# spi_lcd_v1.net
KiCad netlist of a schematic drawn in EAGLE
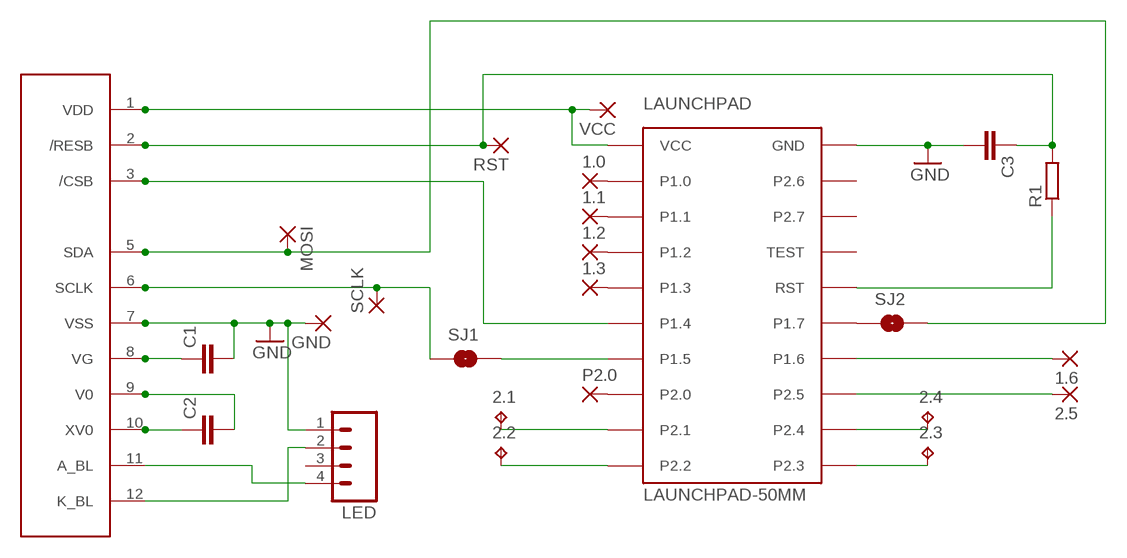
[diagram p0: schematic, sheet 1]

(export (version "E")
  (design (tool "Eeschema 10.0.6"))
  (components
    (comp (ref "1.0")
      (value "2,15/1,0")
      (footprint "eagle-import:2,15_1,0")
      (libsource (lib "eagle-import") (part "2,15/1,0"))
    )
    (comp (ref "1.1")
      (value "2,15/1,0")
      (footprint "eagle-import:2,15_1,0")
      (libsource (lib "eagle-import") (part "2,15/1,0"))
    )
    (comp (ref "1.2")
      (value "2,15/1,0")
      (footprint "eagle-import:2,15_1,0")
      (libsource (lib "eagle-import") (part "2,15/1,0"))
    )
    (comp (ref "1.3")
      (value "2,15/1,0")
      (footprint "eagle-import:2,15_1,0")
      (libsource (lib "eagle-import") (part "2,15/1,0"))
    )
    (comp (ref "1.6")
      (value "2,15/1,0")
      (footprint "eagle-import:2,15_1,0")
      (libsource (lib "eagle-import") (part "2,15/1,0"))
    )
    (comp (ref "2.1")
      (value "TPTP07R")
      (footprint "eagle-import:TP07R")
      (libsource (lib "eagle-import") (part "TPTP07R"))
    )
    (comp (ref "2.2")
      (value "TPTP07R")
      (footprint "eagle-import:TP07R")
      (libsource (lib "eagle-import") (part "TPTP07R"))
    )
    (comp (ref "2.3")
      (value "TPTP07R")
      (footprint "eagle-import:TP07R")
      (libsource (lib "eagle-import") (part "TPTP07R"))
    )
    (comp (ref "2.4")
      (value "TPTP07R")
      (footprint "eagle-import:TP07R")
      (libsource (lib "eagle-import") (part "TPTP07R"))
    )
    (comp (ref "2.5")
      (value "2,15/1,0")
      (footprint "eagle-import:2,15_1,0")
      (libsource (lib "eagle-import") (part "2,15/1,0"))
    )
    (comp (ref "C1")
      (value "CAP1206")
      (footprint "eagle-import:1206")
      (libsource (lib "eagle-import") (part "CAP1206"))
    )
    (comp (ref "C2")
      (value "CAP1206")
      (footprint "eagle-import:1206")
      (libsource (lib "eagle-import") (part "CAP1206"))
    )
    (comp (ref "C3")
      (value "CAP1206")
      (footprint "eagle-import:1206")
      (libsource (lib "eagle-import") (part "CAP1206"))
    )
    (comp (ref "GND")
      (value "2,15/1,0")
      (footprint "eagle-import:2,15_1,0")
      (libsource (lib "eagle-import") (part "2,15/1,0"))
    )
    (comp (ref "LAUNCHPAD")
      (value "LAUNCHPAD-50MM")
      (footprint "eagle-import:LAUNCHPAD-50MM")
      (libsource (lib "eagle-import") (part "LAUNCHPAD-50MM"))
    )
    (comp (ref "LED")
      (value "M04PTH")
      (footprint "eagle-import:1X04")
      (libsource (lib "eagle-import") (part "M04PTH"))
    )
    (comp (ref "MOSI")
      (value "2,15/1,0")
      (footprint "eagle-import:2,15_1,0")
      (libsource (lib "eagle-import") (part "2,15/1,0"))
    )
    (comp (ref "P2.0")
      (value "2,15/1,0")
      (footprint "eagle-import:2,15_1,0")
      (libsource (lib "eagle-import") (part "2,15/1,0"))
    )
    (comp (ref "R1")
      (value "R-EU_R1206")
      (footprint "eagle-import:R1206")
      (libsource (lib "eagle-import") (part "R-EU_R1206"))
    )
    (comp (ref "RST")
      (value "2,15/1,0")
      (footprint "eagle-import:2,15_1,0")
      (libsource (lib "eagle-import") (part "2,15/1,0"))
    )
    (comp (ref "SCLK")
      (value "2,15/1,0")
      (footprint "eagle-import:2,15_1,0")
      (libsource (lib "eagle-import") (part "2,15/1,0"))
    )
    (comp (ref "SJ1")
      (value "SOLDERJUMPERTRACE")
      (footprint "eagle-import:SJ_2S-TRACE")
      (libsource (lib "eagle-import") (part "SOLDERJUMPERTRACE"))
    )
    (comp (ref "SJ2")
      (value "SOLDERJUMPERTRACE")
      (footprint "eagle-import:SJ_2S-TRACE")
      (libsource (lib "eagle-import") (part "SOLDERJUMPERTRACE"))
    )
    (comp (ref "U$1")
      (value "PE9665WRFPE9665WRF-WHOLE")
      (footprint "eagle-import:PE9665WRF")
      (libsource (lib "eagle-import") (part "PE9665WRFPE9665WRF-WHOLE"))
    )
    (comp (ref "VCC")
      (value "2,15/1,0")
      (footprint "eagle-import:2,15_1,0")
      (libsource (lib "eagle-import") (part "2,15/1,0"))
    )
  )
  (nets
    (net (code "1") (name "GND") (class "Default")
      (node (ref "C1") (pin "2") (pinfunction "2_2") (pintype "passive"))
      (node (ref "C3") (pin "2") (pinfunction "2_2") (pintype "passive"))
      (node (ref "GND") (pin "1") (pinfunction "P_1") (pintype "passive"))
      (node (ref "LAUNCHPAD") (pin "GND") (pinfunction "GND_GND") (pintype "power_in"))
      (node (ref "LED") (pin "1") (pinfunction "1_1") (pintype "passive"))
      (node (ref "U$1") (pin "7") (pinfunction "VSS_7") (pintype "bidirectional"))
    )
    (net (code "2") (name "Net-(1.0-P)") (class "Default")
      (node (ref "1.0") (pin "1") (pinfunction "P_1") (pintype "passive"))
      (node (ref "LAUNCHPAD") (pin "P1.0") (pinfunction "P1.0_P1.0") (pintype "bidirectional"))
    )
    (net (code "3") (name "Net-(1.1-P)") (class "Default")
      (node (ref "1.1") (pin "1") (pinfunction "P_1") (pintype "passive"))
      (node (ref "LAUNCHPAD") (pin "P1.1") (pinfunction "P1.1_P1.1") (pintype "bidirectional"))
    )
    (net (code "4") (name "Net-(1.2-P)") (class "Default")
      (node (ref "1.2") (pin "1") (pinfunction "P_1") (pintype "passive"))
      (node (ref "LAUNCHPAD") (pin "P1.2") (pinfunction "P1.2_P1.2") (pintype "bidirectional"))
    )
    (net (code "5") (name "Net-(1.3-P)") (class "Default")
      (node (ref "1.3") (pin "1") (pinfunction "P_1") (pintype "passive"))
      (node (ref "LAUNCHPAD") (pin "P1.3") (pinfunction "P1.3_P1.3") (pintype "bidirectional"))
    )
    (net (code "6") (name "Net-(1.6-P)") (class "Default")
      (node (ref "1.6") (pin "1") (pinfunction "P_1") (pintype "passive"))
      (node (ref "LAUNCHPAD") (pin "P1.6") (pinfunction "P1.6_P1.6") (pintype "bidirectional"))
    )
    (net (code "7") (name "Net-(2.1-PadTP)") (class "Default")
      (node (ref "2.1") (pin "TP") (pinfunction "TP_TP") (pintype "input"))
      (node (ref "LAUNCHPAD") (pin "P2.1") (pinfunction "P2.1_P2.1") (pintype "bidirectional"))
    )
    (net (code "8") (name "Net-(2.2-PadTP)") (class "Default")
      (node (ref "2.2") (pin "TP") (pinfunction "TP_TP") (pintype "input"))
      (node (ref "LAUNCHPAD") (pin "P2.2") (pinfunction "P2.2_P2.2") (pintype "bidirectional"))
    )
    (net (code "9") (name "Net-(2.3-PadTP)") (class "Default")
      (node (ref "2.3") (pin "TP") (pinfunction "TP_TP") (pintype "input"))
      (node (ref "LAUNCHPAD") (pin "P2.3") (pinfunction "P2.3_P2.3") (pintype "bidirectional"))
    )
    (net (code "10") (name "Net-(2.4-PadTP)") (class "Default")
      (node (ref "2.4") (pin "TP") (pinfunction "TP_TP") (pintype "input"))
      (node (ref "LAUNCHPAD") (pin "P2.4") (pinfunction "P2.4_P2.4") (pintype "bidirectional"))
    )
    (net (code "11") (name "Net-(2.5-P)") (class "Default")
      (node (ref "2.5") (pin "1") (pinfunction "P_1") (pintype "passive"))
      (node (ref "LAUNCHPAD") (pin "P2.5") (pinfunction "P2.5_P2.5") (pintype "bidirectional"))
    )
    (net (code "12") (name "Net-(LAUNCHPAD-PadP1.5)") (class "Default")
      (node (ref "LAUNCHPAD") (pin "P1.5") (pinfunction "P1.5_P1.5") (pintype "bidirectional"))
      (node (ref "SJ1") (pin "2") (pinfunction "2_2") (pintype "passive"))
    )
    (net (code "13") (name "Net-(LAUNCHPAD-PadP1.7)") (class "Default")
      (node (ref "LAUNCHPAD") (pin "P1.7") (pinfunction "P1.7_P1.7") (pintype "bidirectional"))
      (node (ref "SJ2") (pin "1") (pinfunction "1_1") (pintype "passive"))
    )
    (net (code "14") (name "Net-(LAUNCHPAD-PadRST)") (class "Default")
      (node (ref "LAUNCHPAD") (pin "RST") (pinfunction "RST_RST") (pintype "bidirectional"))
      (node (ref "R1") (pin "1") (pinfunction "1_1") (pintype "passive"))
    )
    (net (code "15") (name "Net-(MOSI-P)") (class "Default")
      (node (ref "MOSI") (pin "1") (pinfunction "P_1") (pintype "passive"))
      (node (ref "SJ2") (pin "2") (pinfunction "2_2") (pintype "passive"))
      (node (ref "U$1") (pin "5") (pinfunction "SDA_5") (pintype "bidirectional"))
    )
    (net (code "16") (name "Net-(P2.0-P)") (class "Default")
      (node (ref "LAUNCHPAD") (pin "P2.0") (pinfunction "P2.0_P2.0") (pintype "bidirectional"))
      (node (ref "P2.0") (pin "1") (pinfunction "P_1") (pintype "passive"))
    )
    (net (code "17") (name "Net-(RST-P)") (class "Default")
      (node (ref "C3") (pin "1") (pinfunction "1_1") (pintype "passive"))
      (node (ref "R1") (pin "2") (pinfunction "2_2") (pintype "passive"))
      (node (ref "RST") (pin "1") (pinfunction "P_1") (pintype "passive"))
      (node (ref "U$1") (pin "2") (pinfunction "/RESB_2") (pintype "bidirectional"))
    )
    (net (code "18") (name "Net-(SCLK-P)") (class "Default")
      (node (ref "SCLK") (pin "1") (pinfunction "P_1") (pintype "passive"))
      (node (ref "SJ1") (pin "1") (pinfunction "1_1") (pintype "passive"))
      (node (ref "U$1") (pin "6") (pinfunction "SCLK_6") (pintype "bidirectional"))
    )
    (net (code "19") (name "Net-(U$1-A_BL)") (class "Default")
      (node (ref "LED") (pin "4") (pinfunction "4_4") (pintype "passive"))
      (node (ref "U$1") (pin "11") (pinfunction "A_BL_11") (pintype "bidirectional"))
    )
    (net (code "20") (name "Net-(U$1-K_BL)") (class "Default")
      (node (ref "LED") (pin "2") (pinfunction "2_2") (pintype "passive"))
      (node (ref "U$1") (pin "12") (pinfunction "K_BL_12") (pintype "bidirectional"))
    )
    (net (code "21") (name "Net-(U$1-V0)") (class "Default")
      (node (ref "C2") (pin "2") (pinfunction "2_2") (pintype "passive"))
      (node (ref "U$1") (pin "9") (pinfunction "V0_9") (pintype "bidirectional"))
    )
    (net (code "22") (name "Net-(U$1-VDD)") (class "Default")
      (node (ref "LAUNCHPAD") (pin "VCC") (pinfunction "VCC_VCC") (pintype "power_in"))
      (node (ref "U$1") (pin "1") (pinfunction "VDD_1") (pintype "bidirectional"))
      (node (ref "VCC") (pin "1") (pinfunction "P_1") (pintype "passive"))
    )
    (net (code "23") (name "Net-(U$1-VG)") (class "Default")
      (node (ref "C1") (pin "1") (pinfunction "1_1") (pintype "passive"))
      (node (ref "U$1") (pin "8") (pinfunction "VG_8") (pintype "bidirectional"))
    )
    (net (code "24") (name "Net-(U$1-XV0)") (class "Default")
      (node (ref "C2") (pin "1") (pinfunction "1_1") (pintype "passive"))
      (node (ref "U$1") (pin "10") (pinfunction "XV0_10") (pintype "bidirectional"))
    )
    (net (code "25") (name "Net-(U$1-{slash}CSB)") (class "Default")
      (node (ref "LAUNCHPAD") (pin "P1.4") (pinfunction "P1.4_P1.4") (pintype "bidirectional"))
      (node (ref "U$1") (pin "3") (pinfunction "/CSB_3") (pintype "bidirectional"))
    )
    (net (code "26") (name "unconnected-(LAUNCHPAD-PadP2.6)") (class "Default")
      (node (ref "LAUNCHPAD") (pin "P2.6") (pinfunction "P2.6_P2.6") (pintype "bidirectional"))
    )
    (net (code "27") (name "unconnected-(LAUNCHPAD-PadP2.7)") (class "Default")
      (node (ref "LAUNCHPAD") (pin "P2.7") (pinfunction "P2.7_P2.7") (pintype "bidirectional"))
    )
    (net (code "28") (name "unconnected-(LAUNCHPAD-PadTEST)") (class "Default")
      (node (ref "LAUNCHPAD") (pin "TEST") (pinfunction "TEST_TEST") (pintype "bidirectional"))
    )
    (net (code "29") (name "unconnected-(LED-Pad3)") (class "Default")
      (node (ref "LED") (pin "3") (pinfunction "3_3") (pintype "passive"))
    )
  )
)
